# emmc_flash.net
KiCad netlist of a schematic drawn in Altium Designer
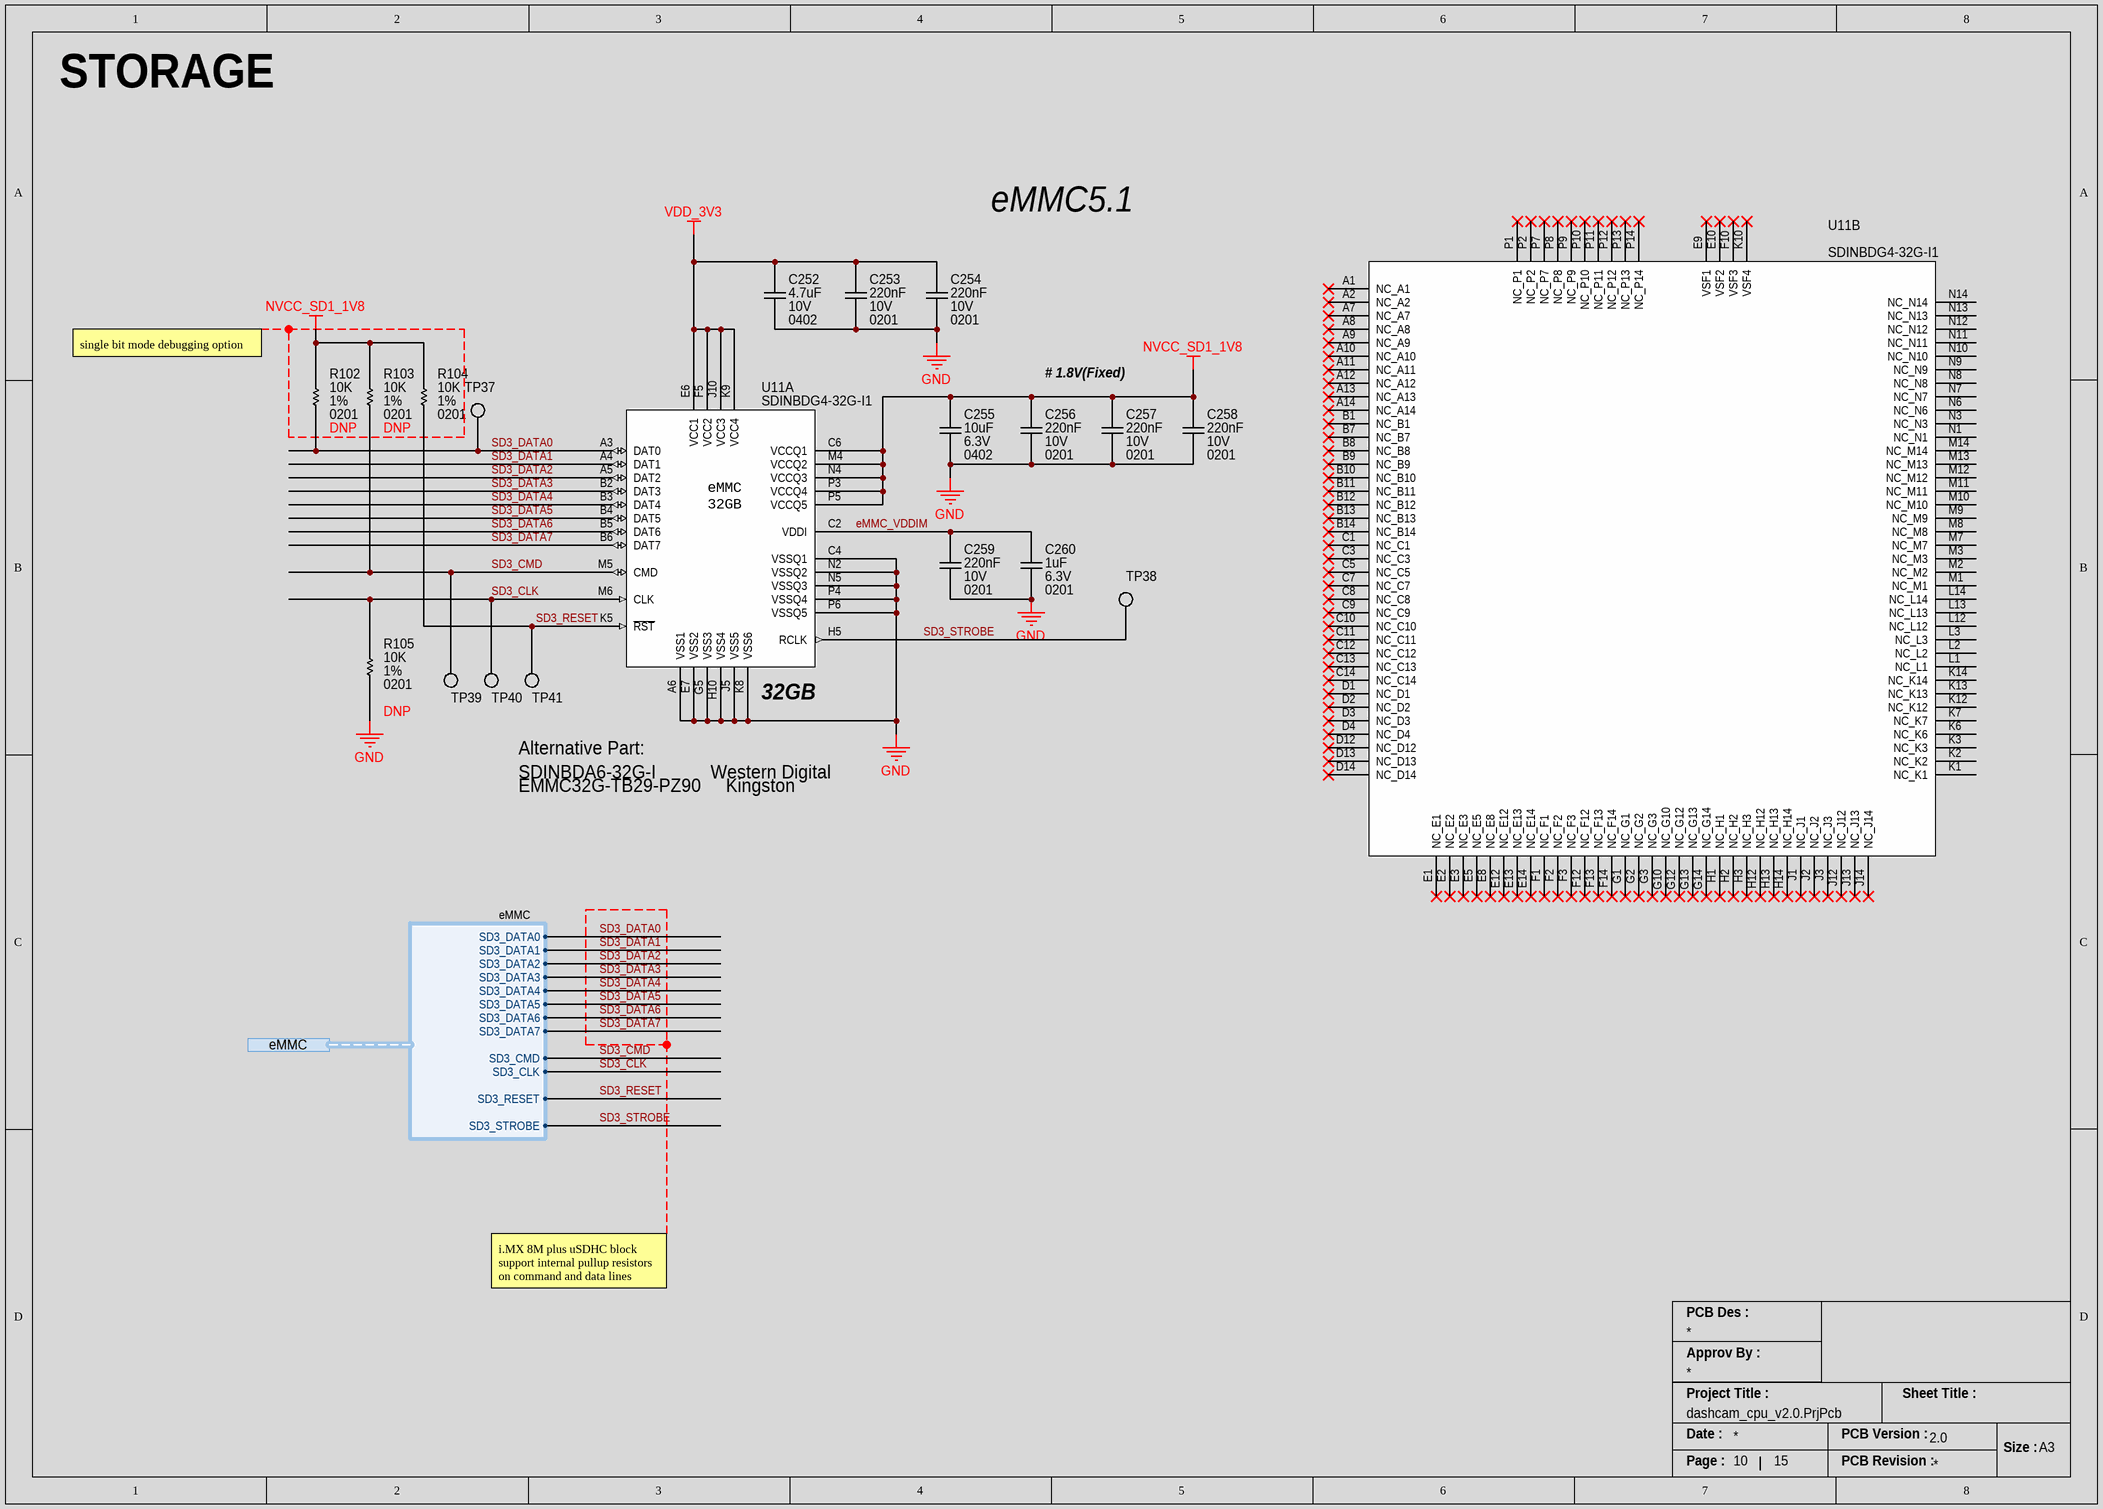
[diagram p0: emmc_flash.SchDoc]

(export (version "E")
  (design (tool "Eeschema 10.0.6"))
  (components
    (comp (ref "C252")
      (value "CL05A475KP5NRNC")
      (footprint "CAP_0402_CAPC1005X05N")
      (description "Multilayer Ceramic Capacitor, 4.7 uF, 10 V, ± 10%, X5R, 0402 [1005 Metric]")
      (fields
        (field (name "MANUFACTURER") "Samsung")
        (field (name "TOLERANCE") "10%")
        (field (name "CAPACITANCE") "4.7uF")
        (field (name "VOLTAGE RATING") "10V")
        (field (name "CASE/PACKAGE") "0402")
      )
      (libsource (lib "Electronic Devices_LIB") (part "CAP_4.7UF_10V_X5R_0402"))
    )
    (comp (ref "C253")
      (value "LMK063BJ224MP-F")
      (footprint "CAP_0201_CAPC0603X03N")
      (description "Multilayer Ceramic Capacitors (High dielectric type), 10V, 0.22 uF, ± 20 %, 0201, X5R, RoHS")
      (fields
        (field (name "MANUFACTURER") "Taiyo Yuden")
        (field (name "TOLERANCE") "20%")
        (field (name "VOLTAGE RATING (DC)") "10V")
        (field (name "CAPACITANCE") "220nF")
        (field (name "CASE/PACKAGE") "0201")
      )
      (libsource (lib "Electronic Devices_LIB") (part "CAP_0.22UF_10V_X5R_0201"))
    )
    (comp (ref "C254")
      (value "LMK063BJ224MP-F")
      (footprint "CAP_0201_CAPC0603X03N")
      (description "Multilayer Ceramic Capacitors (High dielectric type), 10V, 0.22 uF, ± 20 %, 0201, X5R, RoHS")
      (fields
        (field (name "MANUFACTURER") "Taiyo Yuden")
        (field (name "TOLERANCE") "20%")
        (field (name "VOLTAGE RATING (DC)") "10V")
        (field (name "CAPACITANCE") "220nF")
        (field (name "CASE/PACKAGE") "0201")
      )
      (libsource (lib "Electronic Devices_LIB") (part "CAP_0.22UF_10V_X5R_0201"))
    )
    (comp (ref "C255")
      (value "CL05A106MQ5NUNC")
      (footprint "CAP_0402_CAPC1005X05N")
      (description "Cap Ceramic 10uF 6.3V X5R 20% SMD 0402 85C T/R")
      (fields
        (field (name "MANUFACTURER") "Samsung")
        (field (name "TOLERANCE") "20%")
        (field (name "CASE/PACKAGE") "0402")
        (field (name "CAPACITANCE") "10uF")
        (field (name "VOLTAGE RATING") "6.3V")
      )
      (libsource (lib "Electronic Devices_LIB") (part "CAP_10UF_6.3V_X5R_0402"))
    )
    (comp (ref "C256")
      (value "LMK063BJ224MP-F")
      (footprint "CAP_0201_CAPC0603X03N")
      (description "Multilayer Ceramic Capacitors (High dielectric type), 10V, 0.22 uF, ± 20 %, 0201, X5R, RoHS")
      (fields
        (field (name "MANUFACTURER") "Taiyo Yuden")
        (field (name "TOLERANCE") "20%")
        (field (name "VOLTAGE RATING (DC)") "10V")
        (field (name "CAPACITANCE") "220nF")
        (field (name "CASE/PACKAGE") "0201")
      )
      (libsource (lib "Electronic Devices_LIB") (part "CAP_0.22UF_10V_X5R_0201"))
    )
    (comp (ref "C257")
      (value "LMK063BJ224MP-F")
      (footprint "CAP_0201_CAPC0603X03N")
      (description "Multilayer Ceramic Capacitors (High dielectric type), 10V, 0.22 uF, ± 20 %, 0201, X5R, RoHS")
      (fields
        (field (name "MANUFACTURER") "Taiyo Yuden")
        (field (name "TOLERANCE") "20%")
        (field (name "VOLTAGE RATING (DC)") "10V")
        (field (name "CAPACITANCE") "220nF")
        (field (name "CASE/PACKAGE") "0201")
      )
      (libsource (lib "Electronic Devices_LIB") (part "CAP_0.22UF_10V_X5R_0201"))
    )
    (comp (ref "C258")
      (value "LMK063BJ224MP-F")
      (footprint "CAP_0201_CAPC0603X03N")
      (description "Multilayer Ceramic Capacitors (High dielectric type), 10V, 0.22 uF, ± 20 %, 0201, X5R, RoHS")
      (fields
        (field (name "MANUFACTURER") "Taiyo Yuden")
        (field (name "TOLERANCE") "20%")
        (field (name "VOLTAGE RATING (DC)") "10V")
        (field (name "CAPACITANCE") "220nF")
        (field (name "CASE/PACKAGE") "0201")
      )
      (libsource (lib "Electronic Devices_LIB") (part "CAP_0.22UF_10V_X5R_0201"))
    )
    (comp (ref "C259")
      (value "LMK063BJ224MP-F")
      (footprint "CAP_0201_CAPC0603X03N")
      (description "Multilayer Ceramic Capacitors (High dielectric type), 10V, 0.22 uF, ± 20 %, 0201, X5R, RoHS")
      (fields
        (field (name "MANUFACTURER") "Taiyo Yuden")
        (field (name "TOLERANCE") "20%")
        (field (name "VOLTAGE RATING (DC)") "10V")
        (field (name "CAPACITANCE") "220nF")
        (field (name "CASE/PACKAGE") "0201")
      )
      (libsource (lib "Electronic Devices_LIB") (part "CAP_0.22UF_10V_X5R_0201"))
    )
    (comp (ref "C260")
      (value "02016D105MAT2A")
      (footprint "CAP_0201_CAPC0603X03N")
      (description "0201 1 uF 6.3 V ±20 % Tolerance X5R Surface Mount Multilayer Ceramic Capacitor")
      (fields
        (field (name "MANUFACTURER") "Kyocera AVX")
        (field (name "TOLERANCE") "20%")
        (field (name "VOLTAGE RATING (DC)") "6.3V")
        (field (name "CAPACITANCE") "1uF")
        (field (name "CASE/PACKAGE") "0201")
      )
      (libsource (lib "Electronic Devices_LIB") (part "CAP_1UF_6.3V_X5R_0201"))
    )
    (comp (ref "R102")
      (value "RC0201FR-0710KL")
      (footprint "RES_0201_RESC0603X02N")
      (description "SMD Chip Resistor, 10 kOhm, ± 1%, 50 mW, 0201 [0603 Metric], Thick Film, General Purpose")
      (fields
        (field (name "MANUFACTURER") "Yageo")
        (field (name "TOLERANCE") "1%")
        (field (name "RESISTANCE") "10K")
        (field (name "CASE CODE (IMPERIAL)") "0201")
      )
      (libsource (lib "Electronic Devices_LIB") (part "RES_10K_1/12W_1%_0201"))
    )
    (comp (ref "R103")
      (value "RC0201FR-0710KL")
      (footprint "RES_0201_RESC0603X02N")
      (description "SMD Chip Resistor, 10 kOhm, ± 1%, 50 mW, 0201 [0603 Metric], Thick Film, General Purpose")
      (fields
        (field (name "MANUFACTURER") "Yageo")
        (field (name "TOLERANCE") "1%")
        (field (name "RESISTANCE") "10K")
        (field (name "CASE CODE (IMPERIAL)") "0201")
      )
      (libsource (lib "Electronic Devices_LIB") (part "RES_10K_1/12W_1%_0201"))
    )
    (comp (ref "R104")
      (value "RC0201FR-0710KL")
      (footprint "RES_0201_RESC0603X02N")
      (description "SMD Chip Resistor, 10 kOhm, ± 1%, 50 mW, 0201 [0603 Metric], Thick Film, General Purpose")
      (fields
        (field (name "MANUFACTURER") "Yageo")
        (field (name "TOLERANCE") "1%")
        (field (name "RESISTANCE") "10K")
        (field (name "CASE CODE (IMPERIAL)") "0201")
      )
      (libsource (lib "Electronic Devices_LIB") (part "RES_10K_1/12W_1%_0201"))
    )
    (comp (ref "R105")
      (value "RC0201FR-0710KL")
      (footprint "RES_0201_RESC0603X02N")
      (description "SMD Chip Resistor, 10 kOhm, ± 1%, 50 mW, 0201 [0603 Metric], Thick Film, General Purpose")
      (fields
        (field (name "MANUFACTURER") "Yageo")
        (field (name "TOLERANCE") "1%")
        (field (name "RESISTANCE") "10K")
        (field (name "CASE CODE (IMPERIAL)") "0201")
      )
      (libsource (lib "Electronic Devices_LIB") (part "RES_10K_1/12W_1%_0201"))
    )
    (comp (ref "TP37")
      (value "NO COMPONENT")
      (footprint "TP_PAD_0.5MM_SMD_ROUND")
      (description "Test Point, SMD pad, round, 1.5mm, 1.6mm, 3mm diameter")
      (libsource (lib "Electronic Devices_LIB") (part "TP_PAD_SMD_SMALL"))
    )
    (comp (ref "TP38")
      (value "NO COMPONENT")
      (footprint "TP_PAD_0.5MM_SMD_ROUND")
      (description "Test Point, SMD pad, round, 1.5mm, 1.6mm, 3mm diameter")
      (libsource (lib "Electronic Devices_LIB") (part "TP_PAD_SMD_SMALL"))
    )
    (comp (ref "TP39")
      (value "NO COMPONENT")
      (footprint "TP_PAD_0.5MM_SMD_ROUND")
      (description "Test Point, SMD pad, round, 1.5mm, 1.6mm, 3mm diameter")
      (libsource (lib "Electronic Devices_LIB") (part "TP_PAD_SMD_SMALL"))
    )
    (comp (ref "TP40")
      (value "NO COMPONENT")
      (footprint "TP_PAD_0.5MM_SMD_ROUND")
      (description "Test Point, SMD pad, round, 1.5mm, 1.6mm, 3mm diameter")
      (libsource (lib "Electronic Devices_LIB") (part "TP_PAD_SMD_SMALL"))
    )
    (comp (ref "TP41")
      (value "NO COMPONENT")
      (footprint "TP_PAD_0.5MM_SMD_ROUND")
      (description "Test Point, SMD pad, round, 1.5mm, 1.6mm, 3mm diameter")
      (libsource (lib "Electronic Devices_LIB") (part "TP_PAD_SMD_SMALL"))
    )
    (comp (ref "U11")
      (value "SDINBDG4-32G-I1")
      (footprint "IC_MEMORY_eMMC")
      (description "Inand 7250 32GB Industrial Wide Temp -25C+85C EMMC5.1 HS400")
      (fields (field (name "MANUFACTURER") "SanDisk"))
      (libsource (lib "Electronic Devices_LIB") (part "IC_MEMORY_eMMC_SDINBDG4-32G-I1"))
    )
  )
  (nets
    (net (code "2") (name "/SD3_CLK") (class "Default")
      (node (ref "R105") (pin "2") (pinfunction "2_2") (pintype "passive"))
      (node (ref "TP40") (pin "1") (pinfunction "1_1") (pintype "passive"))
      (node (ref "U11") (pin "M6") (pinfunction "CLK_M6") (pintype "input"))
    )
    (net (code "3") (name "/SD3_CMD") (class "Default")
      (node (ref "R103") (pin "1") (pinfunction "1_1") (pintype "passive"))
      (node (ref "TP39") (pin "1") (pinfunction "1_1") (pintype "passive"))
      (node (ref "U11") (pin "M5") (pinfunction "CMD_M5") (pintype "bidirectional"))
    )
    (net (code "4") (name "/SD3_DATA0") (class "Default")
      (node (ref "R102") (pin "1") (pinfunction "1_1") (pintype "passive"))
      (node (ref "TP37") (pin "1") (pinfunction "1_1") (pintype "passive"))
      (node (ref "U11") (pin "A3") (pinfunction "DAT0_A3") (pintype "bidirectional"))
    )
    (net (code "5") (name "/SD3_DATA1") (class "Default")
      (node (ref "U11") (pin "A4") (pinfunction "DAT1_A4") (pintype "bidirectional"))
    )
    (net (code "6") (name "/SD3_DATA2") (class "Default")
      (node (ref "U11") (pin "A5") (pinfunction "DAT2_A5") (pintype "bidirectional"))
    )
    (net (code "7") (name "/SD3_DATA3") (class "Default")
      (node (ref "U11") (pin "B2") (pinfunction "DAT3_B2") (pintype "bidirectional"))
    )
    (net (code "8") (name "/SD3_DATA4") (class "Default")
      (node (ref "U11") (pin "B3") (pinfunction "DAT4_B3") (pintype "bidirectional"))
    )
    (net (code "9") (name "/SD3_DATA5") (class "Default")
      (node (ref "U11") (pin "B4") (pinfunction "DAT5_B4") (pintype "bidirectional"))
    )
    (net (code "10") (name "/SD3_DATA6") (class "Default")
      (node (ref "U11") (pin "B5") (pinfunction "DAT6_B5") (pintype "bidirectional"))
    )
    (net (code "11") (name "/SD3_DATA7") (class "Default")
      (node (ref "U11") (pin "B6") (pinfunction "DAT7_B6") (pintype "bidirectional"))
    )
    (net (code "12") (name "/SD3_RESET") (class "Default")
      (node (ref "R104") (pin "1") (pinfunction "1_1") (pintype "passive"))
      (node (ref "TP41") (pin "1") (pinfunction "1_1") (pintype "passive"))
      (node (ref "U11") (pin "K5") (pinfunction "~{RST}_K5") (pintype "input"))
    )
    (net (code "13") (name "/SD3_STROBE") (class "Default")
      (node (ref "TP38") (pin "1") (pinfunction "1_1") (pintype "passive"))
      (node (ref "U11") (pin "H5") (pinfunction "RCLK_H5") (pintype "output"))
    )
    (net (code "14") (name "/eMMC_VDDIM") (class "Default")
      (node (ref "C259") (pin "2") (pinfunction "2_2") (pintype "passive"))
      (node (ref "C260") (pin "2") (pinfunction "2_2") (pintype "passive"))
      (node (ref "U11") (pin "C2") (pinfunction "VDDI_C2") (pintype "power_in"))
    )
    (net (code "16") (name "GND") (class "Default")
      (node (ref "C252") (pin "1") (pinfunction "1_1") (pintype "passive"))
      (node (ref "C253") (pin "1") (pinfunction "1_1") (pintype "passive"))
      (node (ref "C254") (pin "1") (pinfunction "1_1") (pintype "passive"))
      (node (ref "C255") (pin "1") (pinfunction "1_1") (pintype "passive"))
      (node (ref "C256") (pin "1") (pinfunction "1_1") (pintype "passive"))
      (node (ref "C257") (pin "1") (pinfunction "1_1") (pintype "passive"))
      (node (ref "C258") (pin "1") (pinfunction "1_1") (pintype "passive"))
      (node (ref "C259") (pin "1") (pinfunction "1_1") (pintype "passive"))
      (node (ref "C260") (pin "1") (pinfunction "1_1") (pintype "passive"))
      (node (ref "R105") (pin "1") (pinfunction "1_1") (pintype "passive"))
      (node (ref "U11") (pin "A6") (pinfunction "VSS1_A6") (pintype "power_in"))
      (node (ref "U11") (pin "C4") (pinfunction "VSSQ1_C4") (pintype "power_in"))
      (node (ref "U11") (pin "E7") (pinfunction "VSS2_E7") (pintype "power_in"))
      (node (ref "U11") (pin "G5") (pinfunction "VSS3_G5") (pintype "power_in"))
      (node (ref "U11") (pin "H10") (pinfunction "VSS4_H10") (pintype "power_in"))
      (node (ref "U11") (pin "J5") (pinfunction "VSS5_J5") (pintype "power_in"))
      (node (ref "U11") (pin "K8") (pinfunction "VSS6_K8") (pintype "power_in"))
      (node (ref "U11") (pin "N2") (pinfunction "VSSQ2_N2") (pintype "power_in"))
      (node (ref "U11") (pin "N5") (pinfunction "VSSQ3_N5") (pintype "power_in"))
      (node (ref "U11") (pin "P4") (pinfunction "VSSQ4_P4") (pintype "power_in"))
      (node (ref "U11") (pin "P6") (pinfunction "VSSQ5_P6") (pintype "power_in"))
    )
    (net (code "17") (name "NVCC_SD1_1V8") (class "Default")
      (node (ref "C255") (pin "2") (pinfunction "2_2") (pintype "passive"))
      (node (ref "C256") (pin "2") (pinfunction "2_2") (pintype "passive"))
      (node (ref "C257") (pin "2") (pinfunction "2_2") (pintype "passive"))
      (node (ref "C258") (pin "2") (pinfunction "2_2") (pintype "passive"))
      (node (ref "R102") (pin "2") (pinfunction "2_2") (pintype "passive"))
      (node (ref "R103") (pin "2") (pinfunction "2_2") (pintype "passive"))
      (node (ref "R104") (pin "2") (pinfunction "2_2") (pintype "passive"))
      (node (ref "U11") (pin "C6") (pinfunction "VCCQ1_C6") (pintype "power_in"))
      (node (ref "U11") (pin "M4") (pinfunction "VCCQ2_M4") (pintype "power_in"))
      (node (ref "U11") (pin "N4") (pinfunction "VCCQ3_N4") (pintype "power_in"))
      (node (ref "U11") (pin "P3") (pinfunction "VCCQ4_P3") (pintype "power_in"))
      (node (ref "U11") (pin "P5") (pinfunction "VCCQ5_P5") (pintype "power_in"))
    )
    (net (code "18") (name "VDD_3V3") (class "Default")
      (node (ref "C252") (pin "2") (pinfunction "2_2") (pintype "passive"))
      (node (ref "C253") (pin "2") (pinfunction "2_2") (pintype "passive"))
      (node (ref "C254") (pin "2") (pinfunction "2_2") (pintype "passive"))
      (node (ref "U11") (pin "E6") (pinfunction "VCC1_E6") (pintype "power_in"))
      (node (ref "U11") (pin "F5") (pinfunction "VCC2_F5") (pintype "power_in"))
      (node (ref "U11") (pin "J10") (pinfunction "VCC3_J10") (pintype "power_in"))
      (node (ref "U11") (pin "K9") (pinfunction "VCC4_K9") (pintype "power_in"))
    )
    (net (code "19") (name "unconnected-(U11B-NC_A1-PadA1)") (class "Default")
      (node (ref "U11") (pin "A1") (pinfunction "NC_A1_A1") (pintype "passive+no_connect"))
    )
    (net (code "20") (name "unconnected-(U11B-NC_A2-PadA2)") (class "Default")
      (node (ref "U11") (pin "A2") (pinfunction "NC_A2_A2") (pintype "passive+no_connect"))
    )
    (net (code "21") (name "unconnected-(U11B-NC_A7-PadA7)") (class "Default")
      (node (ref "U11") (pin "A7") (pinfunction "NC_A7_A7") (pintype "passive+no_connect"))
    )
    (net (code "22") (name "unconnected-(U11B-NC_A8-PadA8)") (class "Default")
      (node (ref "U11") (pin "A8") (pinfunction "NC_A8_A8") (pintype "passive+no_connect"))
    )
    (net (code "23") (name "unconnected-(U11B-NC_A9-PadA9)") (class "Default")
      (node (ref "U11") (pin "A9") (pinfunction "NC_A9_A9") (pintype "passive+no_connect"))
    )
    (net (code "24") (name "unconnected-(U11B-NC_A10-PadA10)") (class "Default")
      (node (ref "U11") (pin "A10") (pinfunction "NC_A10_A10") (pintype "passive+no_connect"))
    )
    (net (code "25") (name "unconnected-(U11B-NC_A11-PadA11)") (class "Default")
      (node (ref "U11") (pin "A11") (pinfunction "NC_A11_A11") (pintype "passive+no_connect"))
    )
    (net (code "26") (name "unconnected-(U11B-NC_A12-PadA12)") (class "Default")
      (node (ref "U11") (pin "A12") (pinfunction "NC_A12_A12") (pintype "passive+no_connect"))
    )
    (net (code "27") (name "unconnected-(U11B-NC_A13-PadA13)") (class "Default")
      (node (ref "U11") (pin "A13") (pinfunction "NC_A13_A13") (pintype "passive+no_connect"))
    )
    (net (code "28") (name "unconnected-(U11B-NC_A14-PadA14)") (class "Default")
      (node (ref "U11") (pin "A14") (pinfunction "NC_A14_A14") (pintype "passive+no_connect"))
    )
    (net (code "29") (name "unconnected-(U11B-NC_B1-PadB1)") (class "Default")
      (node (ref "U11") (pin "B1") (pinfunction "NC_B1_B1") (pintype "passive+no_connect"))
    )
    (net (code "30") (name "unconnected-(U11B-NC_B7-PadB7)") (class "Default")
      (node (ref "U11") (pin "B7") (pinfunction "NC_B7_B7") (pintype "passive+no_connect"))
    )
    (net (code "31") (name "unconnected-(U11B-NC_B8-PadB8)") (class "Default")
      (node (ref "U11") (pin "B8") (pinfunction "NC_B8_B8") (pintype "passive+no_connect"))
    )
    (net (code "32") (name "unconnected-(U11B-NC_B9-PadB9)") (class "Default")
      (node (ref "U11") (pin "B9") (pinfunction "NC_B9_B9") (pintype "passive+no_connect"))
    )
    (net (code "33") (name "unconnected-(U11B-NC_B10-PadB10)") (class "Default")
      (node (ref "U11") (pin "B10") (pinfunction "NC_B10_B10") (pintype "passive+no_connect"))
    )
    (net (code "34") (name "unconnected-(U11B-NC_B11-PadB11)") (class "Default")
      (node (ref "U11") (pin "B11") (pinfunction "NC_B11_B11") (pintype "passive+no_connect"))
    )
    (net (code "35") (name "unconnected-(U11B-NC_B12-PadB12)") (class "Default")
      (node (ref "U11") (pin "B12") (pinfunction "NC_B12_B12") (pintype "passive+no_connect"))
    )
    (net (code "36") (name "unconnected-(U11B-NC_B13-PadB13)") (class "Default")
      (node (ref "U11") (pin "B13") (pinfunction "NC_B13_B13") (pintype "passive+no_connect"))
    )
    (net (code "37") (name "unconnected-(U11B-NC_B14-PadB14)") (class "Default")
      (node (ref "U11") (pin "B14") (pinfunction "NC_B14_B14") (pintype "passive+no_connect"))
    )
    (net (code "38") (name "unconnected-(U11B-NC_C1-PadC1)") (class "Default")
      (node (ref "U11") (pin "C1") (pinfunction "NC_C1_C1") (pintype "passive+no_connect"))
    )
    (net (code "39") (name "unconnected-(U11B-NC_C3-PadC3)") (class "Default")
      (node (ref "U11") (pin "C3") (pinfunction "NC_C3_C3") (pintype "passive+no_connect"))
    )
    (net (code "40") (name "unconnected-(U11B-NC_C5-PadC5)") (class "Default")
      (node (ref "U11") (pin "C5") (pinfunction "NC_C5_C5") (pintype "passive+no_connect"))
    )
    (net (code "41") (name "unconnected-(U11B-NC_C7-PadC7)") (class "Default")
      (node (ref "U11") (pin "C7") (pinfunction "NC_C7_C7") (pintype "passive+no_connect"))
    )
    (net (code "42") (name "unconnected-(U11B-NC_C8-PadC8)") (class "Default")
      (node (ref "U11") (pin "C8") (pinfunction "NC_C8_C8") (pintype "passive+no_connect"))
    )
    (net (code "43") (name "unconnected-(U11B-NC_C9-PadC9)") (class "Default")
      (node (ref "U11") (pin "C9") (pinfunction "NC_C9_C9") (pintype "passive+no_connect"))
    )
    (net (code "44") (name "unconnected-(U11B-NC_C10-PadC10)") (class "Default")
      (node (ref "U11") (pin "C10") (pinfunction "NC_C10_C10") (pintype "passive+no_connect"))
    )
    (net (code "45") (name "unconnected-(U11B-NC_C11-PadC11)") (class "Default")
      (node (ref "U11") (pin "C11") (pinfunction "NC_C11_C11") (pintype "passive+no_connect"))
    )
    (net (code "46") (name "unconnected-(U11B-NC_C12-PadC12)") (class "Default")
      (node (ref "U11") (pin "C12") (pinfunction "NC_C12_C12") (pintype "passive+no_connect"))
    )
    (net (code "47") (name "unconnected-(U11B-NC_C13-PadC13)") (class "Default")
      (node (ref "U11") (pin "C13") (pinfunction "NC_C13_C13") (pintype "passive+no_connect"))
    )
    (net (code "48") (name "unconnected-(U11B-NC_C14-PadC14)") (class "Default")
      (node (ref "U11") (pin "C14") (pinfunction "NC_C14_C14") (pintype "passive+no_connect"))
    )
    (net (code "49") (name "unconnected-(U11B-NC_D1-PadD1)") (class "Default")
      (node (ref "U11") (pin "D1") (pinfunction "NC_D1_D1") (pintype "passive+no_connect"))
    )
    (net (code "50") (name "unconnected-(U11B-NC_D2-PadD2)") (class "Default")
      (node (ref "U11") (pin "D2") (pinfunction "NC_D2_D2") (pintype "passive+no_connect"))
    )
    (net (code "51") (name "unconnected-(U11B-NC_D3-PadD3)") (class "Default")
      (node (ref "U11") (pin "D3") (pinfunction "NC_D3_D3") (pintype "passive+no_connect"))
    )
    (net (code "52") (name "unconnected-(U11B-NC_D4-PadD4)") (class "Default")
      (node (ref "U11") (pin "D4") (pinfunction "NC_D4_D4") (pintype "passive+no_connect"))
    )
    (net (code "53") (name "unconnected-(U11B-NC_D12-PadD12)") (class "Default")
      (node (ref "U11") (pin "D12") (pinfunction "NC_D12_D12") (pintype "passive+no_connect"))
    )
    (net (code "54") (name "unconnected-(U11B-NC_D13-PadD13)") (class "Default")
      (node (ref "U11") (pin "D13") (pinfunction "NC_D13_D13") (pintype "passive+no_connect"))
    )
    (net (code "55") (name "unconnected-(U11B-NC_D14-PadD14)") (class "Default")
      (node (ref "U11") (pin "D14") (pinfunction "NC_D14_D14") (pintype "passive+no_connect"))
    )
    (net (code "56") (name "unconnected-(U11B-NC_E1-PadE1)") (class "Default")
      (node (ref "U11") (pin "E1") (pinfunction "NC_E1_E1") (pintype "passive+no_connect"))
    )
    (net (code "57") (name "unconnected-(U11B-NC_E2-PadE2)") (class "Default")
      (node (ref "U11") (pin "E2") (pinfunction "NC_E2_E2") (pintype "passive+no_connect"))
    )
    (net (code "58") (name "unconnected-(U11B-NC_E3-PadE3)") (class "Default")
      (node (ref "U11") (pin "E3") (pinfunction "NC_E3_E3") (pintype "passive+no_connect"))
    )
    (net (code "59") (name "unconnected-(U11B-NC_E5-PadE5)") (class "Default")
      (node (ref "U11") (pin "E5") (pinfunction "NC_E5_E5") (pintype "passive+no_connect"))
    )
    (net (code "60") (name "unconnected-(U11B-NC_E8-PadE8)") (class "Default")
      (node (ref "U11") (pin "E8") (pinfunction "NC_E8_E8") (pintype "passive+no_connect"))
    )
    (net (code "61") (name "unconnected-(U11B-NC_E12-PadE12)") (class "Default")
      (node (ref "U11") (pin "E12") (pinfunction "NC_E12_E12") (pintype "passive+no_connect"))
    )
    (net (code "62") (name "unconnected-(U11B-NC_E13-PadE13)") (class "Default")
      (node (ref "U11") (pin "E13") (pinfunction "NC_E13_E13") (pintype "passive+no_connect"))
    )
    (net (code "63") (name "unconnected-(U11B-NC_E14-PadE14)") (class "Default")
      (node (ref "U11") (pin "E14") (pinfunction "NC_E14_E14") (pintype "passive+no_connect"))
    )
    (net (code "64") (name "unconnected-(U11B-NC_F1-PadF1)") (class "Default")
      (node (ref "U11") (pin "F1") (pinfunction "NC_F1_F1") (pintype "passive+no_connect"))
    )
    (net (code "65") (name "unconnected-(U11B-NC_F2-PadF2)") (class "Default")
      (node (ref "U11") (pin "F2") (pinfunction "NC_F2_F2") (pintype "passive+no_connect"))
    )
    (net (code "66") (name "unconnected-(U11B-NC_F3-PadF3)") (class "Default")
      (node (ref "U11") (pin "F3") (pinfunction "NC_F3_F3") (pintype "passive+no_connect"))
    )
    (net (code "67") (name "unconnected-(U11B-NC_F12-PadF12)") (class "Default")
      (node (ref "U11") (pin "F12") (pinfunction "NC_F12_F12") (pintype "passive+no_connect"))
    )
    (net (code "68") (name "unconnected-(U11B-NC_F13-PadF13)") (class "Default")
      (node (ref "U11") (pin "F13") (pinfunction "NC_F13_F13") (pintype "passive+no_connect"))
    )
    (net (code "69") (name "unconnected-(U11B-NC_F14-PadF14)") (class "Default")
      (node (ref "U11") (pin "F14") (pinfunction "NC_F14_F14") (pintype "passive+no_connect"))
    )
    (net (code "70") (name "unconnected-(U11B-NC_G1-PadG1)") (class "Default")
      (node (ref "U11") (pin "G1") (pinfunction "NC_G1_G1") (pintype "passive+no_connect"))
    )
    (net (code "71") (name "unconnected-(U11B-NC_G2-PadG2)") (class "Default")
      (node (ref "U11") (pin "G2") (pinfunction "NC_G2_G2") (pintype "passive+no_connect"))
    )
    (net (code "72") (name "unconnected-(U11B-NC_G3-PadG3)") (class "Default")
      (node (ref "U11") (pin "G3") (pinfunction "NC_G3_G3") (pintype "passive+no_connect"))
    )
    (net (code "73") (name "unconnected-(U11B-NC_G10-PadG10)") (class "Default")
      (node (ref "U11") (pin "G10") (pinfunction "NC_G10_G10") (pintype "passive+no_connect"))
    )
    (net (code "74") (name "unconnected-(U11B-NC_G12-PadG12)") (class "Default")
      (node (ref "U11") (pin "G12") (pinfunction "NC_G12_G12") (pintype "passive+no_connect"))
    )
    (net (code "75") (name "unconnected-(U11B-NC_G13-PadG13)") (class "Default")
      (node (ref "U11") (pin "G13") (pinfunction "NC_G13_G13") (pintype "passive+no_connect"))
    )
    (net (code "76") (name "unconnected-(U11B-NC_G14-PadG14)") (class "Default")
      (node (ref "U11") (pin "G14") (pinfunction "NC_G14_G14") (pintype "passive+no_connect"))
    )
    (net (code "77") (name "unconnected-(U11B-NC_H1-PadH1)") (class "Default")
      (node (ref "U11") (pin "H1") (pinfunction "NC_H1_H1") (pintype "passive+no_connect"))
    )
    (net (code "78") (name "unconnected-(U11B-NC_H2-PadH2)") (class "Default")
      (node (ref "U11") (pin "H2") (pinfunction "NC_H2_H2") (pintype "passive+no_connect"))
    )
    (net (code "79") (name "unconnected-(U11B-NC_H3-PadH3)") (class "Default")
      (node (ref "U11") (pin "H3") (pinfunction "NC_H3_H3") (pintype "passive+no_connect"))
    )
    (net (code "80") (name "unconnected-(U11B-NC_H12-PadH12)") (class "Default")
      (node (ref "U11") (pin "H12") (pinfunction "NC_H12_H12") (pintype "passive+no_connect"))
    )
    (net (code "81") (name "unconnected-(U11B-NC_H13-PadH13)") (class "Default")
      (node (ref "U11") (pin "H13") (pinfunction "NC_H13_H13") (pintype "passive+no_connect"))
    )
    (net (code "82") (name "unconnected-(U11B-NC_H14-PadH14)") (class "Default")
      (node (ref "U11") (pin "H14") (pinfunction "NC_H14_H14") (pintype "passive+no_connect"))
    )
    (net (code "83") (name "unconnected-(U11B-NC_J1-PadJ1)") (class "Default")
      (node (ref "U11") (pin "J1") (pinfunction "NC_J1_J1") (pintype "passive+no_connect"))
    )
    (net (code "84") (name "unconnected-(U11B-NC_J2-PadJ2)") (class "Default")
      (node (ref "U11") (pin "J2") (pinfunction "NC_J2_J2") (pintype "passive+no_connect"))
    )
    (net (code "85") (name "unconnected-(U11B-NC_J3-PadJ3)") (class "Default")
      (node (ref "U11") (pin "J3") (pinfunction "NC_J3_J3") (pintype "passive+no_connect"))
    )
    (net (code "86") (name "unconnected-(U11B-NC_J12-PadJ12)") (class "Default")
      (node (ref "U11") (pin "J12") (pinfunction "NC_J12_J12") (pintype "passive+no_connect"))
    )
    (net (code "87") (name "unconnected-(U11B-NC_J13-PadJ13)") (class "Default")
      (node (ref "U11") (pin "J13") (pinfunction "NC_J13_J13") (pintype "passive+no_connect"))
    )
    (net (code "88") (name "unconnected-(U11B-NC_J14-PadJ14)") (class "Default")
      (node (ref "U11") (pin "J14") (pinfunction "NC_J14_J14") (pintype "passive+no_connect"))
    )
    (net (code "89") (name "unconnected-(U11B-NC_K1-PadK1)") (class "Default")
      (node (ref "U11") (pin "K1") (pinfunction "NC_K1_K1") (pintype "passive"))
    )
    (net (code "90") (name "unconnected-(U11B-NC_K2-PadK2)") (class "Default")
      (node (ref "U11") (pin "K2") (pinfunction "NC_K2_K2") (pintype "passive"))
    )
    (net (code "91") (name "unconnected-(U11B-NC_K3-PadK3)") (class "Default")
      (node (ref "U11") (pin "K3") (pinfunction "NC_K3_K3") (pintype "passive"))
    )
    (net (code "92") (name "unconnected-(U11B-NC_K6-PadK6)") (class "Default")
      (node (ref "U11") (pin "K6") (pinfunction "NC_K6_K6") (pintype "passive"))
    )
    (net (code "93") (name "unconnected-(U11B-NC_K7-PadK7)") (class "Default")
      (node (ref "U11") (pin "K7") (pinfunction "NC_K7_K7") (pintype "passive"))
    )
    (net (code "94") (name "unconnected-(U11B-NC_K12-PadK12)") (class "Default")
      (node (ref "U11") (pin "K12") (pinfunction "NC_K12_K12") (pintype "passive"))
    )
    (net (code "95") (name "unconnected-(U11B-NC_K13-PadK13)") (class "Default")
      (node (ref "U11") (pin "K13") (pinfunction "NC_K13_K13") (pintype "passive"))
    )
    (net (code "96") (name "unconnected-(U11B-NC_K14-PadK14)") (class "Default")
      (node (ref "U11") (pin "K14") (pinfunction "NC_K14_K14") (pintype "passive"))
    )
    (net (code "97") (name "unconnected-(U11B-NC_L1-PadL1)") (class "Default")
      (node (ref "U11") (pin "L1") (pinfunction "NC_L1_L1") (pintype "passive"))
    )
    (net (code "98") (name "unconnected-(U11B-NC_L2-PadL2)") (class "Default")
      (node (ref "U11") (pin "L2") (pinfunction "NC_L2_L2") (pintype "passive"))
    )
    (net (code "99") (name "unconnected-(U11B-NC_L3-PadL3)") (class "Default")
      (node (ref "U11") (pin "L3") (pinfunction "NC_L3_L3") (pintype "passive"))
    )
    (net (code "100") (name "unconnected-(U11B-NC_L12-PadL12)") (class "Default")
      (node (ref "U11") (pin "L12") (pinfunction "NC_L12_L12") (pintype "passive"))
    )
    (net (code "101") (name "unconnected-(U11B-NC_L13-PadL13)") (class "Default")
      (node (ref "U11") (pin "L13") (pinfunction "NC_L13_L13") (pintype "passive"))
    )
    (net (code "102") (name "unconnected-(U11B-NC_L14-PadL14)") (class "Default")
      (node (ref "U11") (pin "L14") (pinfunction "NC_L14_L14") (pintype "passive"))
    )
    (net (code "103") (name "unconnected-(U11B-NC_M1-PadM1)") (class "Default")
      (node (ref "U11") (pin "M1") (pinfunction "NC_M1_M1") (pintype "passive"))
    )
    (net (code "104") (name "unconnected-(U11B-NC_M2-PadM2)") (class "Default")
      (node (ref "U11") (pin "M2") (pinfunction "NC_M2_M2") (pintype "passive"))
    )
    (net (code "105") (name "unconnected-(U11B-NC_M3-PadM3)") (class "Default")
      (node (ref "U11") (pin "M3") (pinfunction "NC_M3_M3") (pintype "passive"))
    )
    (net (code "106") (name "unconnected-(U11B-NC_M7-PadM7)") (class "Default")
      (node (ref "U11") (pin "M7") (pinfunction "NC_M7_M7") (pintype "passive"))
    )
    (net (code "107") (name "unconnected-(U11B-NC_M8-PadM8)") (class "Default")
      (node (ref "U11") (pin "M8") (pinfunction "NC_M8_M8") (pintype "passive"))
    )
    (net (code "108") (name "unconnected-(U11B-NC_M9-PadM9)") (class "Default")
      (node (ref "U11") (pin "M9") (pinfunction "NC_M9_M9") (pintype "passive"))
    )
    (net (code "109") (name "unconnected-(U11B-NC_M10-PadM10)") (class "Default")
      (node (ref "U11") (pin "M10") (pinfunction "NC_M10_M10") (pintype "passive"))
    )
    (net (code "110") (name "unconnected-(U11B-NC_M11-PadM11)") (class "Default")
      (node (ref "U11") (pin "M11") (pinfunction "NC_M11_M11") (pintype "passive"))
    )
    (net (code "111") (name "unconnected-(U11B-NC_M12-PadM12)") (class "Default")
      (node (ref "U11") (pin "M12") (pinfunction "NC_M12_M12") (pintype "passive"))
    )
    (net (code "112") (name "unconnected-(U11B-NC_M13-PadM13)") (class "Default")
      (node (ref "U11") (pin "M13") (pinfunction "NC_M13_M13") (pintype "passive"))
    )
    (net (code "113") (name "unconnected-(U11B-NC_M14-PadM14)") (class "Default")
      (node (ref "U11") (pin "M14") (pinfunction "NC_M14_M14") (pintype "passive"))
    )
    (net (code "114") (name "unconnected-(U11B-NC_N1-PadN1)") (class "Default")
      (node (ref "U11") (pin "N1") (pinfunction "NC_N1_N1") (pintype "passive"))
    )
    (net (code "115") (name "unconnected-(U11B-NC_N3-PadN3)") (class "Default")
      (node (ref "U11") (pin "N3") (pinfunction "NC_N3_N3") (pintype "passive"))
    )
    (net (code "116") (name "unconnected-(U11B-NC_N6-PadN6)") (class "Default")
      (node (ref "U11") (pin "N6") (pinfunction "NC_N6_N6") (pintype "passive"))
    )
    (net (code "117") (name "unconnected-(U11B-NC_N7-PadN7)") (class "Default")
      (node (ref "U11") (pin "N7") (pinfunction "NC_N7_N7") (pintype "passive"))
    )
    (net (code "118") (name "unconnected-(U11B-NC_N8-PadN8)") (class "Default")
      (node (ref "U11") (pin "N8") (pinfunction "NC_N8_N8") (pintype "passive"))
    )
    (net (code "119") (name "unconnected-(U11B-NC_N9-PadN9)") (class "Default")
      (node (ref "U11") (pin "N9") (pinfunction "NC_N9_N9") (pintype "passive"))
    )
    (net (code "120") (name "unconnected-(U11B-NC_N10-PadN10)") (class "Default")
      (node (ref "U11") (pin "N10") (pinfunction "NC_N10_N10") (pintype "passive"))
    )
    (net (code "121") (name "unconnected-(U11B-NC_N11-PadN11)") (class "Default")
      (node (ref "U11") (pin "N11") (pinfunction "NC_N11_N11") (pintype "passive"))
    )
    (net (code "122") (name "unconnected-(U11B-NC_N12-PadN12)") (class "Default")
      (node (ref "U11") (pin "N12") (pinfunction "NC_N12_N12") (pintype "passive"))
    )
    (net (code "123") (name "unconnected-(U11B-NC_N13-PadN13)") (class "Default")
      (node (ref "U11") (pin "N13") (pinfunction "NC_N13_N13") (pintype "passive"))
    )
    (net (code "124") (name "unconnected-(U11B-NC_N14-PadN14)") (class "Default")
      (node (ref "U11") (pin "N14") (pinfunction "NC_N14_N14") (pintype "passive"))
    )
    (net (code "125") (name "unconnected-(U11B-NC_P1-PadP1)") (class "Default")
      (node (ref "U11") (pin "P1") (pinfunction "NC_P1_P1") (pintype "passive+no_connect"))
    )
    (net (code "126") (name "unconnected-(U11B-NC_P2-PadP2)") (class "Default")
      (node (ref "U11") (pin "P2") (pinfunction "NC_P2_P2") (pintype "passive+no_connect"))
    )
    (net (code "127") (name "unconnected-(U11B-NC_P7-PadP7)") (class "Default")
      (node (ref "U11") (pin "P7") (pinfunction "NC_P7_P7") (pintype "passive+no_connect"))
    )
    (net (code "128") (name "unconnected-(U11B-NC_P8-PadP8)") (class "Default")
      (node (ref "U11") (pin "P8") (pinfunction "NC_P8_P8") (pintype "passive+no_connect"))
    )
    (net (code "129") (name "unconnected-(U11B-NC_P9-PadP9)") (class "Default")
      (node (ref "U11") (pin "P9") (pinfunction "NC_P9_P9") (pintype "passive+no_connect"))
    )
    (net (code "130") (name "unconnected-(U11B-NC_P10-PadP10)") (class "Default")
      (node (ref "U11") (pin "P10") (pinfunction "NC_P10_P10") (pintype "passive+no_connect"))
    )
    (net (code "131") (name "unconnected-(U11B-NC_P11-PadP11)") (class "Default")
      (node (ref "U11") (pin "P11") (pinfunction "NC_P11_P11") (pintype "passive+no_connect"))
    )
    (net (code "132") (name "unconnected-(U11B-NC_P12-PadP12)") (class "Default")
      (node (ref "U11") (pin "P12") (pinfunction "NC_P12_P12") (pintype "passive+no_connect"))
    )
    (net (code "133") (name "unconnected-(U11B-NC_P13-PadP13)") (class "Default")
      (node (ref "U11") (pin "P13") (pinfunction "NC_P13_P13") (pintype "passive+no_connect"))
    )
    (net (code "134") (name "unconnected-(U11B-NC_P14-PadP14)") (class "Default")
      (node (ref "U11") (pin "P14") (pinfunction "NC_P14_P14") (pintype "passive+no_connect"))
    )
    (net (code "135") (name "unconnected-(U11B-VSF1-PadE9)") (class "Default")
      (node (ref "U11") (pin "E9") (pinfunction "VSF1_E9") (pintype "passive+no_connect"))
    )
    (net (code "136") (name "unconnected-(U11B-VSF2-PadE10)") (class "Default")
      (node (ref "U11") (pin "E10") (pinfunction "VSF2_E10") (pintype "passive+no_connect"))
    )
    (net (code "137") (name "unconnected-(U11B-VSF3-PadF10)") (class "Default")
      (node (ref "U11") (pin "F10") (pinfunction "VSF3_F10") (pintype "passive+no_connect"))
    )
    (net (code "138") (name "unconnected-(U11B-VSF4-PadK10)") (class "Default")
      (node (ref "U11") (pin "K10") (pinfunction "VSF4_K10") (pintype "passive+no_connect"))
    )
  )
)
